# LED.net
KiCad netlist of a schematic drawn in Altium Designer
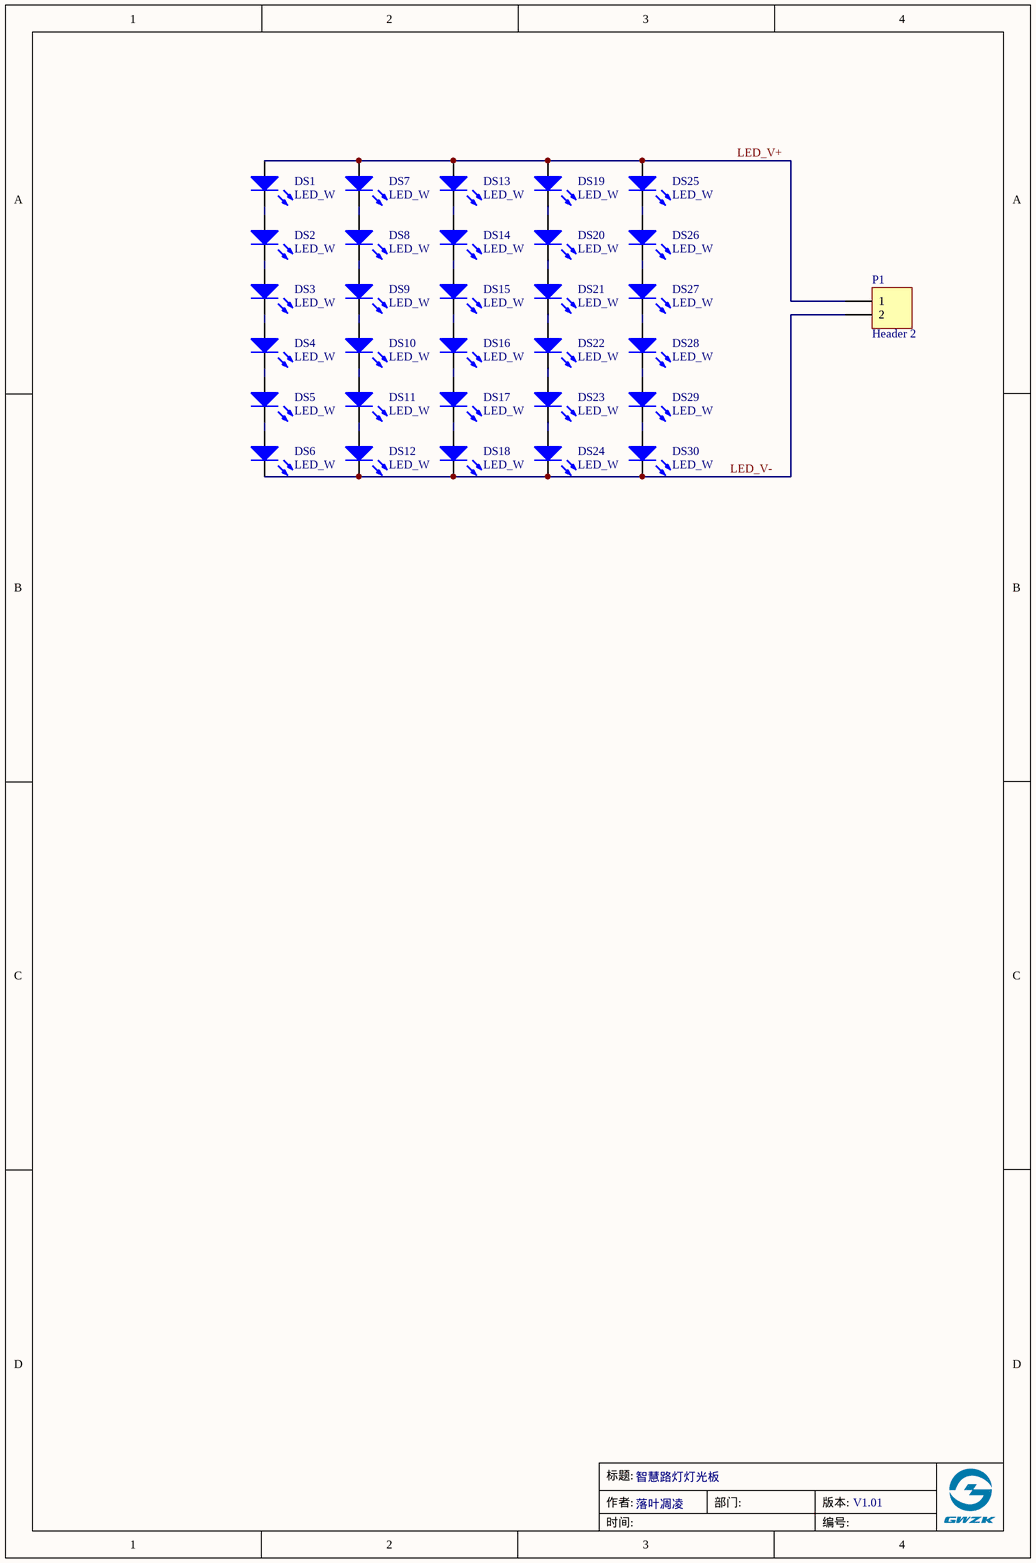
[diagram p0: LED.SchDoc]

(export (version "E")
  (design (tool "Eeschema 10.0.6"))
  (components
    (comp (ref "DS1")
      (value "LED_W")
      (footprint "LED 3528")
      (description "Typical RED, GREEN, YELLOW, AMBER GaAs LED")
      (fields (field (name "PUBLISHER") "Altium Limited"))
      (libsource (lib "原理图库") (part "LED"))
    )
    (comp (ref "DS2")
      (value "LED_W")
      (footprint "LED 3528")
      (description "Typical RED, GREEN, YELLOW, AMBER GaAs LED")
      (fields (field (name "PUBLISHER") "Altium Limited"))
      (libsource (lib "原理图库") (part "LED"))
    )
    (comp (ref "DS3")
      (value "LED_W")
      (footprint "LED 3528")
      (description "Typical RED, GREEN, YELLOW, AMBER GaAs LED")
      (fields (field (name "PUBLISHER") "Altium Limited"))
      (libsource (lib "原理图库") (part "LED"))
    )
    (comp (ref "DS4")
      (value "LED_W")
      (footprint "LED 3528")
      (description "Typical RED, GREEN, YELLOW, AMBER GaAs LED")
      (fields (field (name "PUBLISHER") "Altium Limited"))
      (libsource (lib "原理图库") (part "LED"))
    )
    (comp (ref "DS5")
      (value "LED_W")
      (footprint "LED 3528")
      (description "Typical RED, GREEN, YELLOW, AMBER GaAs LED")
      (fields (field (name "PUBLISHER") "Altium Limited"))
      (libsource (lib "原理图库") (part "LED"))
    )
    (comp (ref "DS6")
      (value "LED_W")
      (footprint "LED 3528")
      (description "Typical RED, GREEN, YELLOW, AMBER GaAs LED")
      (fields (field (name "PUBLISHER") "Altium Limited"))
      (libsource (lib "原理图库") (part "LED"))
    )
    (comp (ref "DS7")
      (value "LED_W")
      (footprint "LED 3528")
      (description "Typical RED, GREEN, YELLOW, AMBER GaAs LED")
      (fields (field (name "PUBLISHER") "Altium Limited"))
      (libsource (lib "原理图库") (part "LED"))
    )
    (comp (ref "DS8")
      (value "LED_W")
      (footprint "LED 3528")
      (description "Typical RED, GREEN, YELLOW, AMBER GaAs LED")
      (fields (field (name "PUBLISHER") "Altium Limited"))
      (libsource (lib "原理图库") (part "LED"))
    )
    (comp (ref "DS9")
      (value "LED_W")
      (footprint "LED 3528")
      (description "Typical RED, GREEN, YELLOW, AMBER GaAs LED")
      (fields (field (name "PUBLISHER") "Altium Limited"))
      (libsource (lib "原理图库") (part "LED"))
    )
    (comp (ref "DS10")
      (value "LED_W")
      (footprint "LED 3528")
      (description "Typical RED, GREEN, YELLOW, AMBER GaAs LED")
      (fields (field (name "PUBLISHER") "Altium Limited"))
      (libsource (lib "原理图库") (part "LED"))
    )
    (comp (ref "DS11")
      (value "LED_W")
      (footprint "LED 3528")
      (description "Typical RED, GREEN, YELLOW, AMBER GaAs LED")
      (fields (field (name "PUBLISHER") "Altium Limited"))
      (libsource (lib "原理图库") (part "LED"))
    )
    (comp (ref "DS12")
      (value "LED_W")
      (footprint "LED 3528")
      (description "Typical RED, GREEN, YELLOW, AMBER GaAs LED")
      (fields (field (name "PUBLISHER") "Altium Limited"))
      (libsource (lib "原理图库") (part "LED"))
    )
    (comp (ref "DS13")
      (value "LED_W")
      (footprint "LED 3528")
      (description "Typical RED, GREEN, YELLOW, AMBER GaAs LED")
      (fields (field (name "PUBLISHER") "Altium Limited"))
      (libsource (lib "原理图库") (part "LED"))
    )
    (comp (ref "DS14")
      (value "LED_W")
      (footprint "LED 3528")
      (description "Typical RED, GREEN, YELLOW, AMBER GaAs LED")
      (fields (field (name "PUBLISHER") "Altium Limited"))
      (libsource (lib "原理图库") (part "LED"))
    )
    (comp (ref "DS15")
      (value "LED_W")
      (footprint "LED 3528")
      (description "Typical RED, GREEN, YELLOW, AMBER GaAs LED")
      (fields (field (name "PUBLISHER") "Altium Limited"))
      (libsource (lib "原理图库") (part "LED"))
    )
    (comp (ref "DS16")
      (value "LED_W")
      (footprint "LED 3528")
      (description "Typical RED, GREEN, YELLOW, AMBER GaAs LED")
      (fields (field (name "PUBLISHER") "Altium Limited"))
      (libsource (lib "原理图库") (part "LED"))
    )
    (comp (ref "DS17")
      (value "LED_W")
      (footprint "LED 3528")
      (description "Typical RED, GREEN, YELLOW, AMBER GaAs LED")
      (fields (field (name "PUBLISHER") "Altium Limited"))
      (libsource (lib "原理图库") (part "LED"))
    )
    (comp (ref "DS18")
      (value "LED_W")
      (footprint "LED 3528")
      (description "Typical RED, GREEN, YELLOW, AMBER GaAs LED")
      (fields (field (name "PUBLISHER") "Altium Limited"))
      (libsource (lib "原理图库") (part "LED"))
    )
    (comp (ref "DS19")
      (value "LED_W")
      (footprint "LED 3528")
      (description "Typical RED, GREEN, YELLOW, AMBER GaAs LED")
      (fields (field (name "PUBLISHER") "Altium Limited"))
      (libsource (lib "原理图库") (part "LED"))
    )
    (comp (ref "DS20")
      (value "LED_W")
      (footprint "LED 3528")
      (description "Typical RED, GREEN, YELLOW, AMBER GaAs LED")
      (fields (field (name "PUBLISHER") "Altium Limited"))
      (libsource (lib "原理图库") (part "LED"))
    )
    (comp (ref "DS21")
      (value "LED_W")
      (footprint "LED 3528")
      (description "Typical RED, GREEN, YELLOW, AMBER GaAs LED")
      (fields (field (name "PUBLISHER") "Altium Limited"))
      (libsource (lib "原理图库") (part "LED"))
    )
    (comp (ref "DS22")
      (value "LED_W")
      (footprint "LED 3528")
      (description "Typical RED, GREEN, YELLOW, AMBER GaAs LED")
      (fields (field (name "PUBLISHER") "Altium Limited"))
      (libsource (lib "原理图库") (part "LED"))
    )
    (comp (ref "DS23")
      (value "LED_W")
      (footprint "LED 3528")
      (description "Typical RED, GREEN, YELLOW, AMBER GaAs LED")
      (fields (field (name "PUBLISHER") "Altium Limited"))
      (libsource (lib "原理图库") (part "LED"))
    )
    (comp (ref "DS24")
      (value "LED_W")
      (footprint "LED 3528")
      (description "Typical RED, GREEN, YELLOW, AMBER GaAs LED")
      (fields (field (name "PUBLISHER") "Altium Limited"))
      (libsource (lib "原理图库") (part "LED"))
    )
    (comp (ref "DS25")
      (value "LED_W")
      (footprint "LED 3528")
      (description "Typical RED, GREEN, YELLOW, AMBER GaAs LED")
      (fields (field (name "PUBLISHER") "Altium Limited"))
      (libsource (lib "原理图库") (part "LED"))
    )
    (comp (ref "DS26")
      (value "LED_W")
      (footprint "LED 3528")
      (description "Typical RED, GREEN, YELLOW, AMBER GaAs LED")
      (fields (field (name "PUBLISHER") "Altium Limited"))
      (libsource (lib "原理图库") (part "LED"))
    )
    (comp (ref "DS27")
      (value "LED_W")
      (footprint "LED 3528")
      (description "Typical RED, GREEN, YELLOW, AMBER GaAs LED")
      (fields (field (name "PUBLISHER") "Altium Limited"))
      (libsource (lib "原理图库") (part "LED"))
    )
    (comp (ref "DS28")
      (value "LED_W")
      (footprint "LED 3528")
      (description "Typical RED, GREEN, YELLOW, AMBER GaAs LED")
      (fields (field (name "PUBLISHER") "Altium Limited"))
      (libsource (lib "原理图库") (part "LED"))
    )
    (comp (ref "DS29")
      (value "LED_W")
      (footprint "LED 3528")
      (description "Typical RED, GREEN, YELLOW, AMBER GaAs LED")
      (fields (field (name "PUBLISHER") "Altium Limited"))
      (libsource (lib "原理图库") (part "LED"))
    )
    (comp (ref "DS30")
      (value "LED_W")
      (footprint "LED 3528")
      (description "Typical RED, GREEN, YELLOW, AMBER GaAs LED")
      (fields (field (name "PUBLISHER") "Altium Limited"))
      (libsource (lib "原理图库") (part "LED"))
    )
    (comp (ref "P1")
      (value "Header 2")
      (footprint "KF2EDGK5.0-LI-2P")
      (description "Header, 2-Pin")
      (fields (field (name "PUBLISHER") "Altium Limited"))
      (libsource (lib "Miscellaneous Connectors") (part "Header 2"))
    )
  )
  (nets
    (net (code "1") (name "/LED_V+") (class "Default")
      (node (ref "DS1") (pin "A") (pinfunction "A_A") (pintype "passive"))
      (node (ref "DS13") (pin "A") (pinfunction "A_A") (pintype "passive"))
      (node (ref "DS19") (pin "A") (pinfunction "A_A") (pintype "passive"))
      (node (ref "DS25") (pin "A") (pinfunction "A_A") (pintype "passive"))
      (node (ref "DS7") (pin "A") (pinfunction "A_A") (pintype "passive"))
      (node (ref "P1") (pin "1") (pinfunction "1_1") (pintype "passive"))
    )
    (net (code "2") (name "/LED_V-") (class "Default")
      (node (ref "DS12") (pin "K") (pinfunction "K_K") (pintype "passive"))
      (node (ref "DS18") (pin "K") (pinfunction "K_K") (pintype "passive"))
      (node (ref "DS24") (pin "K") (pinfunction "K_K") (pintype "passive"))
      (node (ref "DS30") (pin "K") (pinfunction "K_K") (pintype "passive"))
      (node (ref "DS6") (pin "K") (pinfunction "K_K") (pintype "passive"))
      (node (ref "P1") (pin "2") (pinfunction "2_2") (pintype "passive"))
    )
    (net (code "3") (name "Net-(DS1-PadK)") (class "Default")
      (node (ref "DS1") (pin "K") (pinfunction "K_K") (pintype "passive"))
      (node (ref "DS2") (pin "A") (pinfunction "A_A") (pintype "passive"))
    )
    (net (code "4") (name "Net-(DS2-PadK)") (class "Default")
      (node (ref "DS2") (pin "K") (pinfunction "K_K") (pintype "passive"))
      (node (ref "DS3") (pin "A") (pinfunction "A_A") (pintype "passive"))
    )
    (net (code "5") (name "Net-(DS3-PadK)") (class "Default")
      (node (ref "DS3") (pin "K") (pinfunction "K_K") (pintype "passive"))
      (node (ref "DS4") (pin "A") (pinfunction "A_A") (pintype "passive"))
    )
    (net (code "6") (name "Net-(DS4-PadK)") (class "Default")
      (node (ref "DS4") (pin "K") (pinfunction "K_K") (pintype "passive"))
      (node (ref "DS5") (pin "A") (pinfunction "A_A") (pintype "passive"))
    )
    (net (code "7") (name "Net-(DS5-PadK)") (class "Default")
      (node (ref "DS5") (pin "K") (pinfunction "K_K") (pintype "passive"))
      (node (ref "DS6") (pin "A") (pinfunction "A_A") (pintype "passive"))
    )
    (net (code "8") (name "Net-(DS7-PadK)") (class "Default")
      (node (ref "DS7") (pin "K") (pinfunction "K_K") (pintype "passive"))
      (node (ref "DS8") (pin "A") (pinfunction "A_A") (pintype "passive"))
    )
    (net (code "9") (name "Net-(DS8-PadK)") (class "Default")
      (node (ref "DS8") (pin "K") (pinfunction "K_K") (pintype "passive"))
      (node (ref "DS9") (pin "A") (pinfunction "A_A") (pintype "passive"))
    )
    (net (code "10") (name "Net-(DS10-PadA)") (class "Default")
      (node (ref "DS10") (pin "A") (pinfunction "A_A") (pintype "passive"))
      (node (ref "DS9") (pin "K") (pinfunction "K_K") (pintype "passive"))
    )
    (net (code "11") (name "Net-(DS10-PadK)") (class "Default")
      (node (ref "DS10") (pin "K") (pinfunction "K_K") (pintype "passive"))
      (node (ref "DS11") (pin "A") (pinfunction "A_A") (pintype "passive"))
    )
    (net (code "12") (name "Net-(DS11-PadK)") (class "Default")
      (node (ref "DS11") (pin "K") (pinfunction "K_K") (pintype "passive"))
      (node (ref "DS12") (pin "A") (pinfunction "A_A") (pintype "passive"))
    )
    (net (code "13") (name "Net-(DS13-PadK)") (class "Default")
      (node (ref "DS13") (pin "K") (pinfunction "K_K") (pintype "passive"))
      (node (ref "DS14") (pin "A") (pinfunction "A_A") (pintype "passive"))
    )
    (net (code "14") (name "Net-(DS14-PadK)") (class "Default")
      (node (ref "DS14") (pin "K") (pinfunction "K_K") (pintype "passive"))
      (node (ref "DS15") (pin "A") (pinfunction "A_A") (pintype "passive"))
    )
    (net (code "15") (name "Net-(DS15-PadK)") (class "Default")
      (node (ref "DS15") (pin "K") (pinfunction "K_K") (pintype "passive"))
      (node (ref "DS16") (pin "A") (pinfunction "A_A") (pintype "passive"))
    )
    (net (code "16") (name "Net-(DS16-PadK)") (class "Default")
      (node (ref "DS16") (pin "K") (pinfunction "K_K") (pintype "passive"))
      (node (ref "DS17") (pin "A") (pinfunction "A_A") (pintype "passive"))
    )
    (net (code "17") (name "Net-(DS17-PadK)") (class "Default")
      (node (ref "DS17") (pin "K") (pinfunction "K_K") (pintype "passive"))
      (node (ref "DS18") (pin "A") (pinfunction "A_A") (pintype "passive"))
    )
    (net (code "18") (name "Net-(DS19-PadK)") (class "Default")
      (node (ref "DS19") (pin "K") (pinfunction "K_K") (pintype "passive"))
      (node (ref "DS20") (pin "A") (pinfunction "A_A") (pintype "passive"))
    )
    (net (code "19") (name "Net-(DS20-PadK)") (class "Default")
      (node (ref "DS20") (pin "K") (pinfunction "K_K") (pintype "passive"))
      (node (ref "DS21") (pin "A") (pinfunction "A_A") (pintype "passive"))
    )
    (net (code "20") (name "Net-(DS21-PadK)") (class "Default")
      (node (ref "DS21") (pin "K") (pinfunction "K_K") (pintype "passive"))
      (node (ref "DS22") (pin "A") (pinfunction "A_A") (pintype "passive"))
    )
    (net (code "21") (name "Net-(DS22-PadK)") (class "Default")
      (node (ref "DS22") (pin "K") (pinfunction "K_K") (pintype "passive"))
      (node (ref "DS23") (pin "A") (pinfunction "A_A") (pintype "passive"))
    )
    (net (code "22") (name "Net-(DS23-PadK)") (class "Default")
      (node (ref "DS23") (pin "K") (pinfunction "K_K") (pintype "passive"))
      (node (ref "DS24") (pin "A") (pinfunction "A_A") (pintype "passive"))
    )
    (net (code "23") (name "Net-(DS25-PadK)") (class "Default")
      (node (ref "DS25") (pin "K") (pinfunction "K_K") (pintype "passive"))
      (node (ref "DS26") (pin "A") (pinfunction "A_A") (pintype "passive"))
    )
    (net (code "24") (name "Net-(DS26-PadK)") (class "Default")
      (node (ref "DS26") (pin "K") (pinfunction "K_K") (pintype "passive"))
      (node (ref "DS27") (pin "A") (pinfunction "A_A") (pintype "passive"))
    )
    (net (code "25") (name "Net-(DS27-PadK)") (class "Default")
      (node (ref "DS27") (pin "K") (pinfunction "K_K") (pintype "passive"))
      (node (ref "DS28") (pin "A") (pinfunction "A_A") (pintype "passive"))
    )
    (net (code "26") (name "Net-(DS28-PadK)") (class "Default")
      (node (ref "DS28") (pin "K") (pinfunction "K_K") (pintype "passive"))
      (node (ref "DS29") (pin "A") (pinfunction "A_A") (pintype "passive"))
    )
    (net (code "27") (name "Net-(DS29-PadK)") (class "Default")
      (node (ref "DS29") (pin "K") (pinfunction "K_K") (pintype "passive"))
      (node (ref "DS30") (pin "A") (pinfunction "A_A") (pintype "passive"))
    )
  )
)
